# Power.net
KiCad netlist of a schematic drawn in Altium Designer
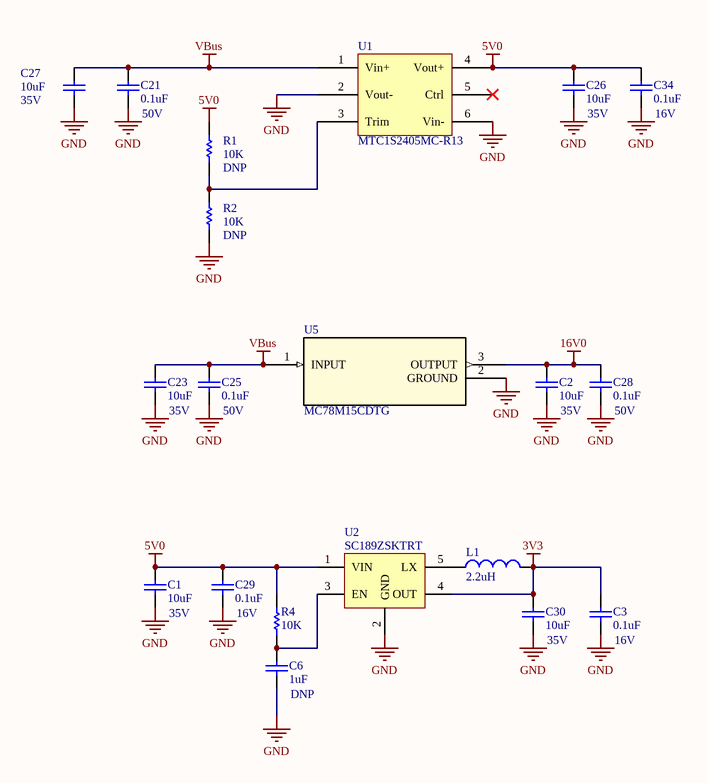
[diagram p0: Power.SchDoc]

(export (version "E")
  (design (tool "Eeschema 10.0.6"))
  (components
    (comp (ref "C1")
      (value "10uF")
      (footprint "CAPC2012X145N")
      (description "CAP")
      (fields (field (name "TOLERANCE") "±10%") (field (name "VOLTAGE - RATED") "35V"))
      (libsource (lib "GMLintLib") (part "CAP"))
    )
    (comp (ref "C2")
      (value "10uF")
      (footprint "CAPC2012X145N")
      (description "CAP")
      (fields (field (name "TOLERANCE") "±10%") (field (name "VOLTAGE - RATED") "35V"))
      (libsource (lib "GMLintLib") (part "CAP"))
    )
    (comp (ref "C3")
      (value "0.1uF")
      (footprint "CAPC1005(0402)N")
      (description "CAP CER 0.1UF 16V X5R 0402")
      (fields (field (name "TOLERANCE") "±10%") (field (name "VOLTAGE - RATED") "16V"))
      (libsource (lib "GMLintLib") (part "CAP"))
    )
    (comp (ref "C6")
      (value "1uF")
      (footprint "CAPC1005(0402)N")
      (description "CAP")
      (fields (field (name "TOLERANCE") "±10%") (field (name "DNP") "DNP"))
      (libsource (lib "GMLintLib") (part "CAP"))
    )
    (comp (ref "C21")
      (value "0.1uF")
      (footprint "CAPC1005(0402)N")
      (description "CAP CER 0.1UF 16V X5R 0402")
      (fields (field (name "TOLERANCE") "±10%") (field (name "VOLTAGE - RATED") "50V"))
      (libsource (lib "GMLintLib") (part "CAP"))
    )
    (comp (ref "C23")
      (value "10uF")
      (footprint "CAPC2012X145N")
      (description "CAP")
      (fields (field (name "TOLERANCE") "±10%") (field (name "VOLTAGE - RATED") "35V"))
      (libsource (lib "GMLintLib") (part "CAP"))
    )
    (comp (ref "C25")
      (value "0.1uF")
      (footprint "CAPC1005(0402)N")
      (description "CAP CER 0.1UF 16V X5R 0402")
      (fields (field (name "TOLERANCE") "±10%") (field (name "VOLTAGE - RATED") "50V"))
      (libsource (lib "GMLintLib") (part "CAP"))
    )
    (comp (ref "C26")
      (value "10uF")
      (footprint "CAPC2012X145N")
      (description "CAP")
      (fields (field (name "TOLERANCE") "±10%") (field (name "VOLTAGE - RATED") "35V"))
      (libsource (lib "GMLintLib") (part "CAP"))
    )
    (comp (ref "C27")
      (value "10uF")
      (footprint "CAPC2012X145N")
      (description "CAP")
      (fields (field (name "TOLERANCE") "±10%") (field (name "VOLTAGE - RATED") "35V"))
      (libsource (lib "GMLintLib") (part "CAP"))
    )
    (comp (ref "C28")
      (value "0.1uF")
      (footprint "CAPC1005(0402)N")
      (description "CAP CER 0.1UF 16V X5R 0402")
      (fields (field (name "TOLERANCE") "±10%") (field (name "VOLTAGE - RATED") "50V"))
      (libsource (lib "GMLintLib") (part "CAP"))
    )
    (comp (ref "C29")
      (value "0.1uF")
      (footprint "CAPC1005(0402)N")
      (description "CAP CER 0.1UF 16V X5R 0402")
      (fields (field (name "TOLERANCE") "±10%") (field (name "VOLTAGE - RATED") "16V"))
      (libsource (lib "GMLintLib") (part "CAP"))
    )
    (comp (ref "C30")
      (value "10uF")
      (footprint "CAPC2012X145N")
      (description "CAP")
      (fields (field (name "TOLERANCE") "±10%") (field (name "VOLTAGE - RATED") "35V"))
      (libsource (lib "GMLintLib") (part "CAP"))
    )
    (comp (ref "C34")
      (value "0.1uF")
      (footprint "CAPC1005(0402)N")
      (description "CAP CER 0.1UF 16V X5R 0402")
      (fields (field (name "TOLERANCE") "±10%") (field (name "VOLTAGE - RATED") "16V"))
      (libsource (lib "GMLintLib") (part "CAP"))
    )
    (comp (ref "L1")
      (value "2.2uH")
      (footprint "IND_TAIYO_NRS401")
      (description "Inductor, fixed, 2.2UH 1.5A 98 MOHM SMD")
      (fields (field (name "TOLERANCE") "20%"))
      (libsource (lib "GMLintLib") (part "IND"))
    )
    (comp (ref "R1")
      (value "10K")
      (footprint "0402")
      (description "Resistor")
      (fields
        (field (name "DNP") "DNP")
        (field (name "Comment") "Res1")
        (field (name "PUBLISHER") "Altium Limited")
      )
      (libsource (lib "Miscellaneous Devices") (part "Res1"))
    )
    (comp (ref "R2")
      (value "10K")
      (footprint "0402")
      (description "Resistor")
      (fields
        (field (name "DNP") "DNP")
        (field (name "Comment") "Res1")
        (field (name "PUBLISHER") "Altium Limited")
      )
      (libsource (lib "Miscellaneous Devices") (part "Res1"))
    )
    (comp (ref "R4")
      (value "10K")
      (footprint "RESC1005(0402)N")
      (description "Resistor, Chip")
      (libsource (lib "GMLintLib") (part "RES"))
    )
    (comp (ref "U1")
      (value "MTC1S2405MC-R13")
      (footprint "MTC1S2405MC-R13")
      (libsource (lib "LegBoard") (part "MTC1S2405MC-R13"))
    )
    (comp (ref "U2")
      (value "SC189ZSKTRT")
      (footprint "SOT23-5")
      (description "IC, Buck Converter, SC189ZSKTRT")
      (libsource (lib "GMLintLib") (part "VREG-DCDC-SC189"))
    )
    (comp (ref "U5")
      (value "MC78M15CDTG")
      (footprint "DPAK-3")
      (description "No Description Available")
      (fields (field (name "COPYRIGHT") "Copyright (C) 2016 Accelerated Designs. All rights reserved"))
      (libsource (lib "LegBoard") (part "MC78M15CDTG"))
    )
  )
  (nets
    (net (code "1") (name "3V3") (class "Default")
      (node (ref "C3") (pin "2") (pinfunction "2_2") (pintype "passive"))
      (node (ref "C30") (pin "1") (pinfunction "1_1") (pintype "passive"))
      (node (ref "L1") (pin "2") (pinfunction "2_2") (pintype "passive"))
      (node (ref "U2") (pin "4") (pinfunction "OUT_4") (pintype "passive"))
    )
    (net (code "2") (name "5V0") (class "Default")
      (node (ref "C1") (pin "1") (pinfunction "1_1") (pintype "passive"))
      (node (ref "C26") (pin "1") (pinfunction "1_1") (pintype "passive"))
      (node (ref "C29") (pin "2") (pinfunction "2_2") (pintype "passive"))
      (node (ref "C34") (pin "2") (pinfunction "2_2") (pintype "passive"))
      (node (ref "R1") (pin "2") (pinfunction "2_2") (pintype "passive"))
      (node (ref "R4") (pin "2") (pinfunction "2_2") (pintype "passive"))
      (node (ref "U1") (pin "4") (pinfunction "Vout+_4") (pintype "passive"))
      (node (ref "U2") (pin "1") (pinfunction "VIN_1") (pintype "passive"))
    )
    (net (code "3") (name "16V0") (class "Default")
      (node (ref "C2") (pin "1") (pinfunction "1_1") (pintype "passive"))
      (node (ref "C28") (pin "2") (pinfunction "2_2") (pintype "passive"))
      (node (ref "U5") (pin "3") (pinfunction "OUTPUT_3") (pintype "output"))
    )
    (net (code "4") (name "GND") (class "Default")
      (node (ref "C1") (pin "2") (pinfunction "2_2") (pintype "passive"))
      (node (ref "C2") (pin "2") (pinfunction "2_2") (pintype "passive"))
      (node (ref "C21") (pin "1") (pinfunction "1_1") (pintype "passive"))
      (node (ref "C23") (pin "2") (pinfunction "2_2") (pintype "passive"))
      (node (ref "C25") (pin "1") (pinfunction "1_1") (pintype "passive"))
      (node (ref "C26") (pin "2") (pinfunction "2_2") (pintype "passive"))
      (node (ref "C27") (pin "2") (pinfunction "2_2") (pintype "passive"))
      (node (ref "C28") (pin "1") (pinfunction "1_1") (pintype "passive"))
      (node (ref "C29") (pin "1") (pinfunction "1_1") (pintype "passive"))
      (node (ref "C3") (pin "1") (pinfunction "1_1") (pintype "passive"))
      (node (ref "C30") (pin "2") (pinfunction "2_2") (pintype "passive"))
      (node (ref "C34") (pin "1") (pinfunction "1_1") (pintype "passive"))
      (node (ref "C6") (pin "2") (pinfunction "2_2") (pintype "passive"))
      (node (ref "R2") (pin "1") (pinfunction "1_1") (pintype "passive"))
      (node (ref "U1") (pin "2") (pinfunction "Vout-_2") (pintype "passive"))
      (node (ref "U1") (pin "6") (pinfunction "Vin-_6") (pintype "passive"))
      (node (ref "U2") (pin "2") (pinfunction "GND_2") (pintype "passive"))
      (node (ref "U5") (pin "2") (pinfunction "GROUND_2") (pintype "power_in"))
    )
    (net (code "5") (name "Net-(U1-Trim)") (class "Default")
      (node (ref "R1") (pin "1") (pinfunction "1_1") (pintype "passive"))
      (node (ref "R2") (pin "2") (pinfunction "2_2") (pintype "passive"))
      (node (ref "U1") (pin "3") (pinfunction "Trim_3") (pintype "passive"))
    )
    (net (code "6") (name "Net-(U2-EN)") (class "Default")
      (node (ref "C6") (pin "1") (pinfunction "1_1") (pintype "passive"))
      (node (ref "R4") (pin "1") (pinfunction "1_1") (pintype "passive"))
      (node (ref "U2") (pin "3") (pinfunction "EN_3") (pintype "passive"))
    )
    (net (code "7") (name "Net-(U2-LX)") (class "Default")
      (node (ref "L1") (pin "1") (pinfunction "1_1") (pintype "passive"))
      (node (ref "U2") (pin "5") (pinfunction "LX_5") (pintype "passive"))
    )
    (net (code "8") (name "VBus") (class "Default")
      (node (ref "C21") (pin "2") (pinfunction "2_2") (pintype "passive"))
      (node (ref "C23") (pin "1") (pinfunction "1_1") (pintype "passive"))
      (node (ref "C25") (pin "2") (pinfunction "2_2") (pintype "passive"))
      (node (ref "C27") (pin "1") (pinfunction "1_1") (pintype "passive"))
      (node (ref "U1") (pin "1") (pinfunction "Vin+_1") (pintype "passive"))
      (node (ref "U5") (pin "1") (pinfunction "INPUT_1") (pintype "input"))
    )
    (net (code "9") (name "unconnected-(U1-Ctrl-Pad5)") (class "Default")
      (node (ref "U1") (pin "5") (pinfunction "Ctrl_5") (pintype "passive+no_connect"))
    )
  )
)
